# eZ-FET_lite.net
KiCad netlist of a schematic drawn in EAGLE
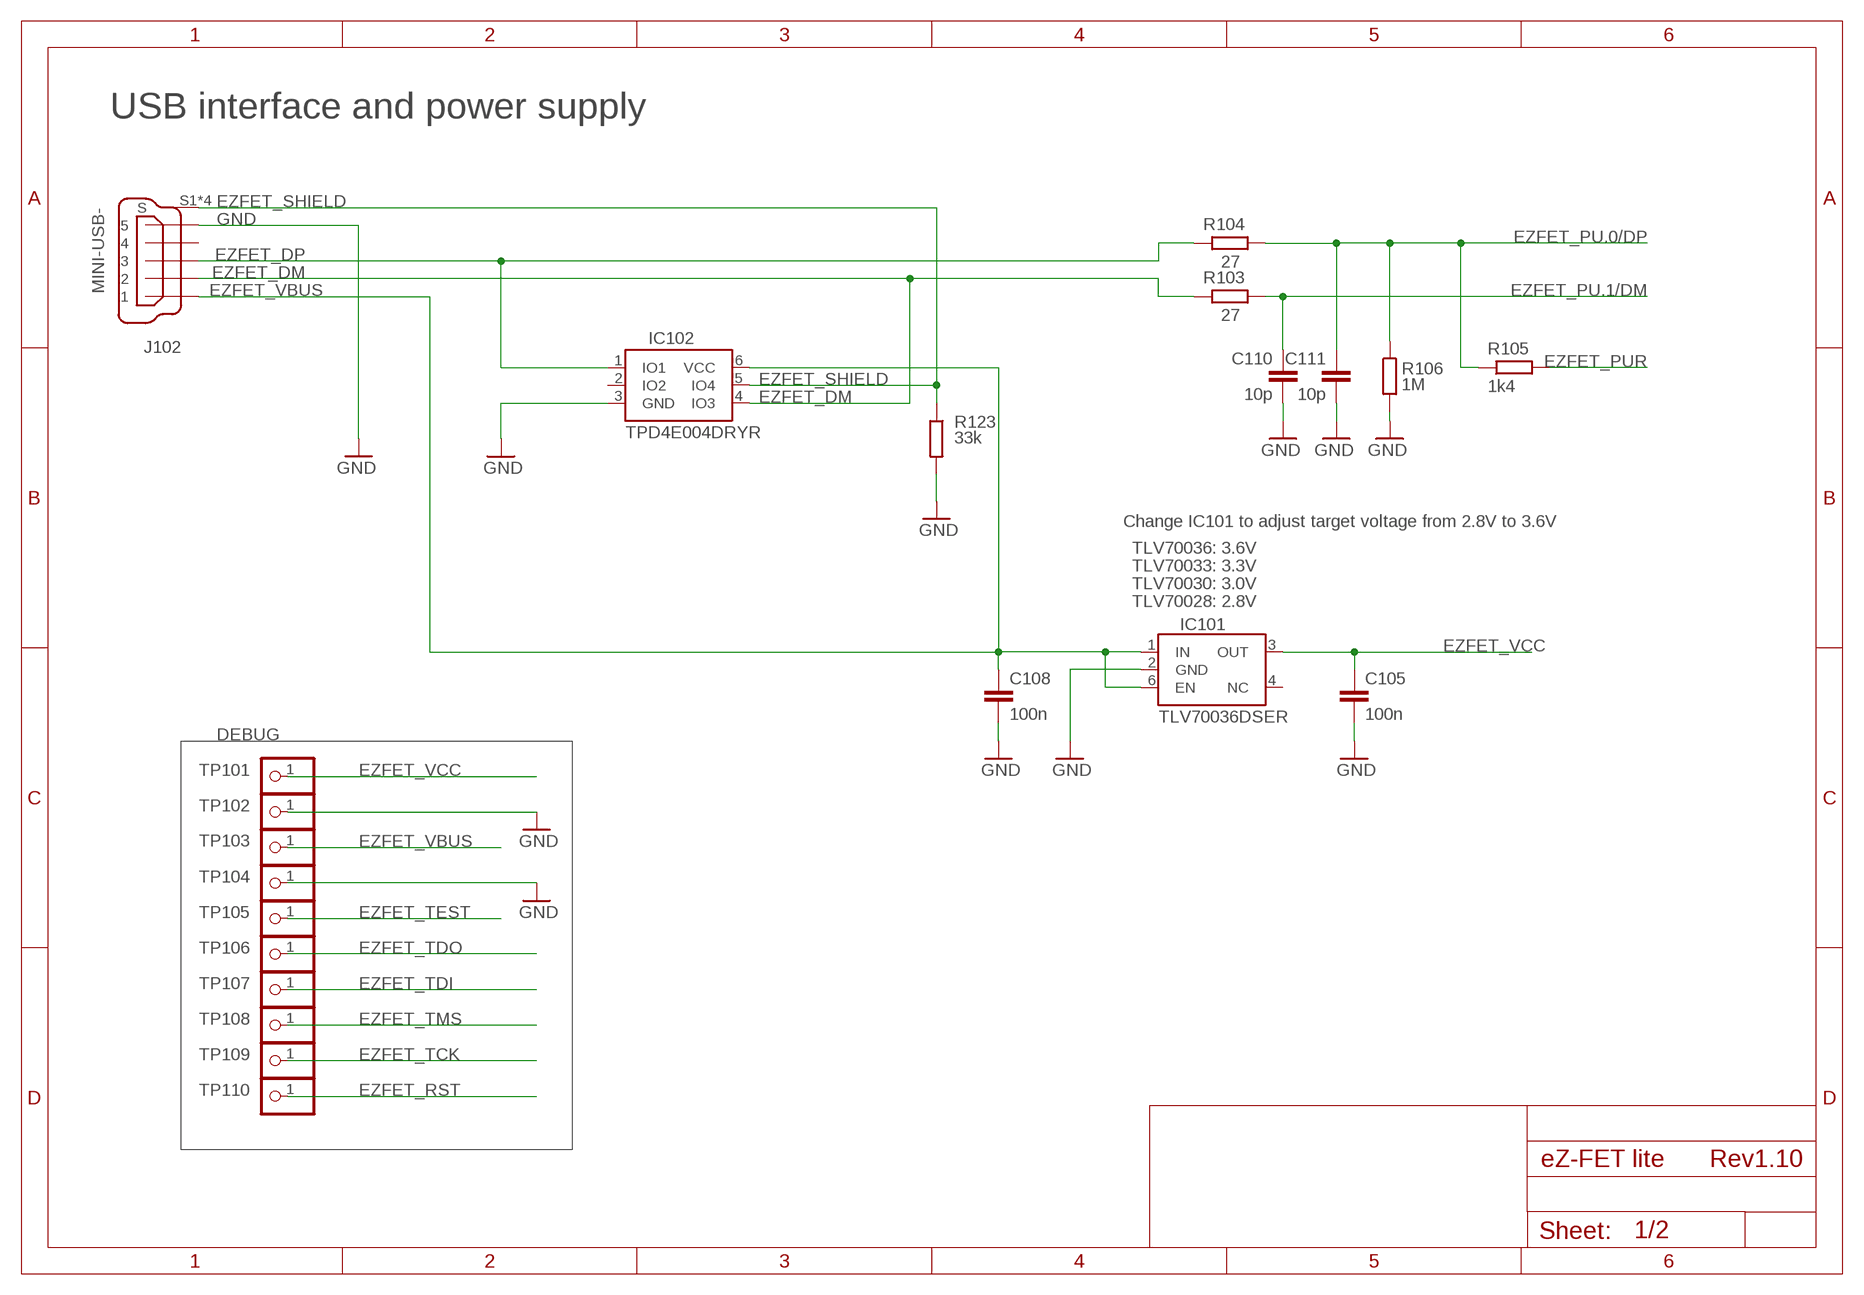
[diagram p0: schematic, sheet 1]
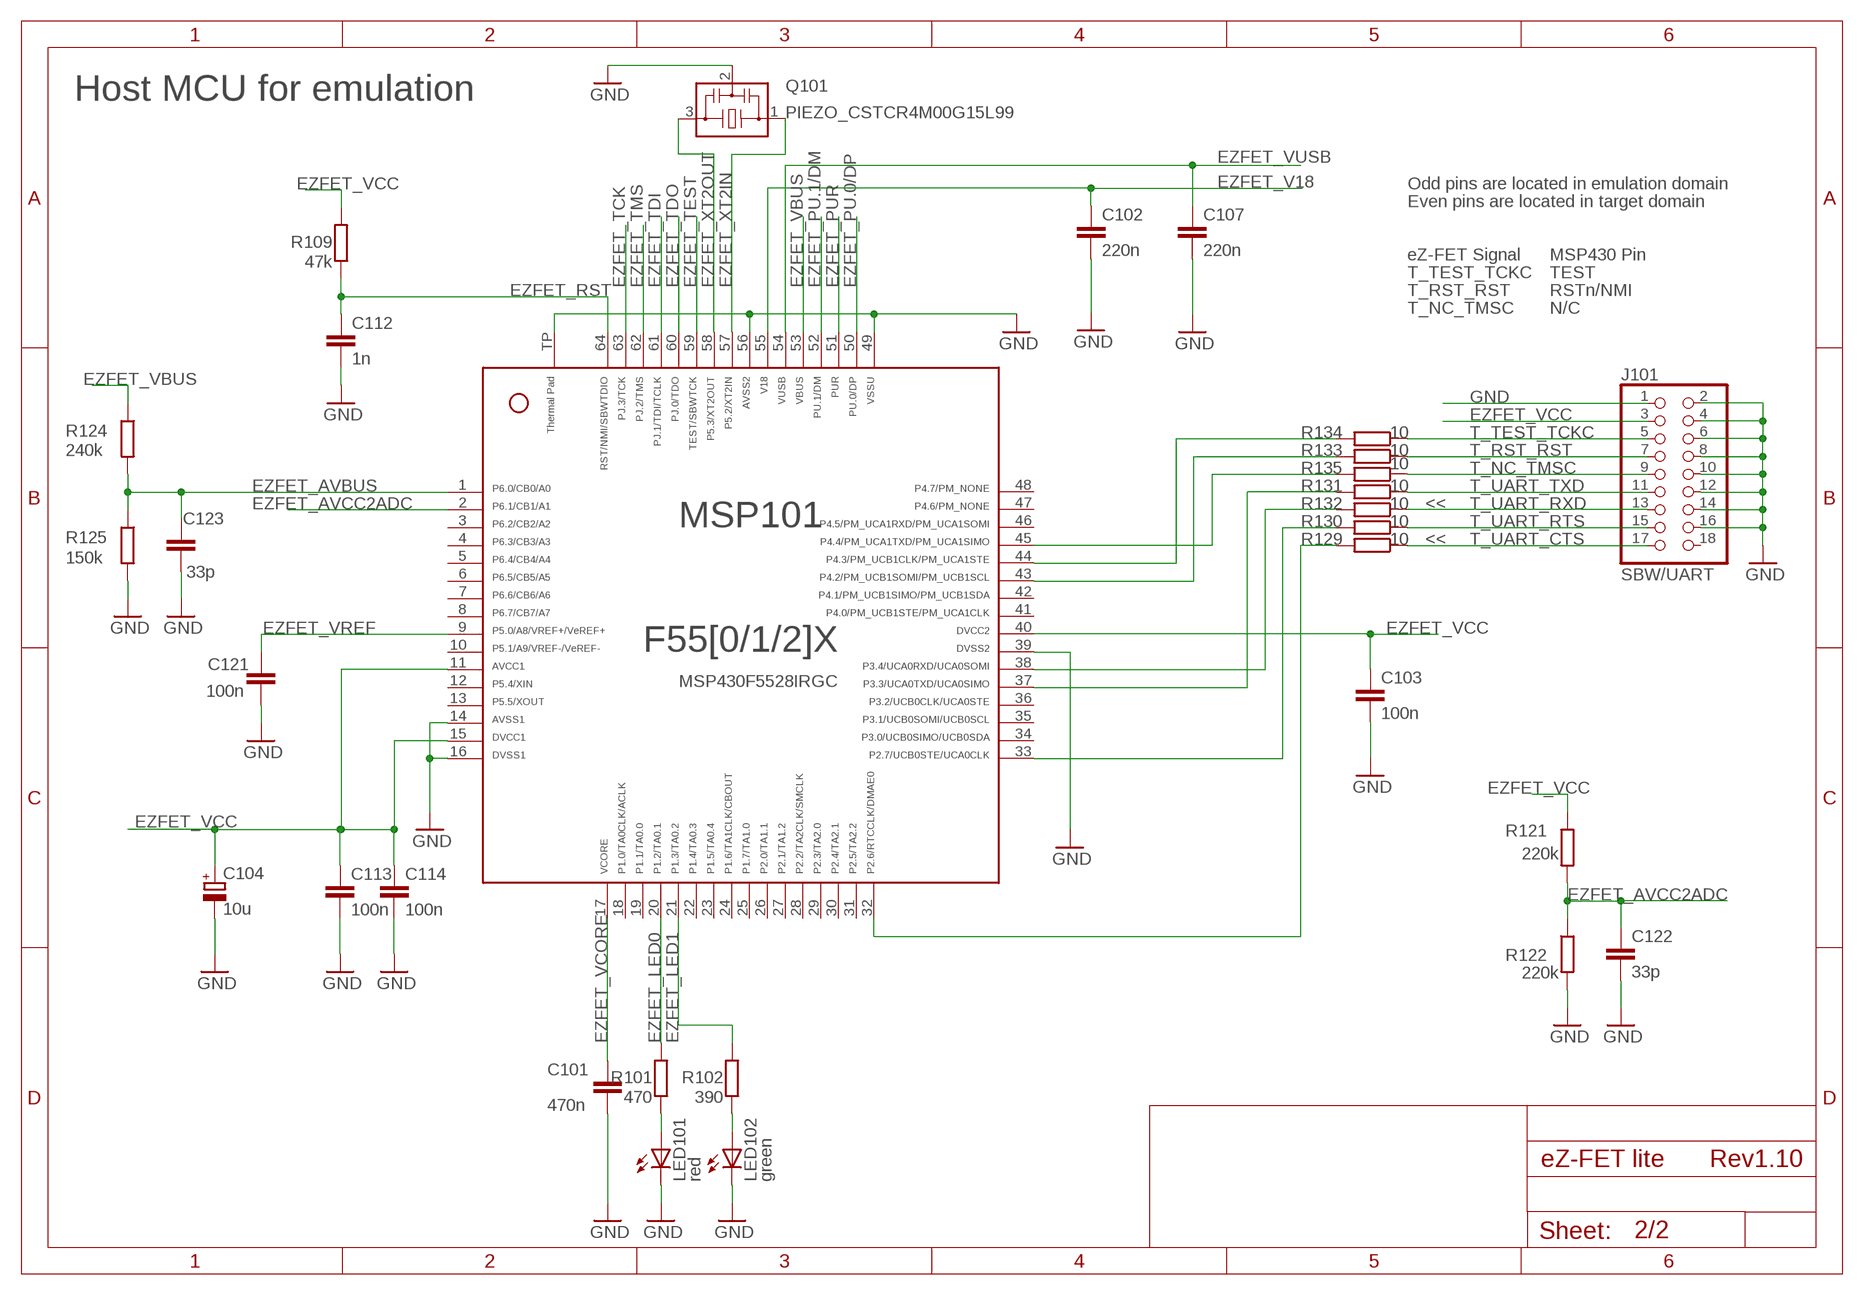
[diagram p1: schematic, sheet 2]

(export (version "E")
  (design (tool "Eeschema 10.0.6"))
  (components
    (comp (ref "C105")
      (value "100n")
      (footprint "eagle-import:C0402")
      (libsource (lib "eagle-import") (part "C-EUC0402"))
    )
    (comp (ref "C108")
      (value "100n")
      (footprint "eagle-import:C0402")
      (libsource (lib "eagle-import") (part "C-EUC0402"))
    )
    (comp (ref "C110")
      (value "10p")
      (footprint "eagle-import:C0402")
      (libsource (lib "eagle-import") (part "C-EUC0402"))
    )
    (comp (ref "C111")
      (value "10p")
      (footprint "eagle-import:C0402")
      (libsource (lib "eagle-import") (part "C-EUC0402"))
    )
    (comp (ref "IC101")
      (value "TLV70036DSER")
      (footprint "eagle-import:SON(DRY)6")
      (libsource (lib "eagle-import") (part "TLV700XX"))
    )
    (comp (ref "IC102")
      (value "TPD4E004DRYR")
      (footprint "eagle-import:SON(DRY)6")
      (libsource (lib "eagle-import") (part "TPD4E004"))
    )
    (comp (ref "J102")
      (value "MINI-USB-")
      (footprint "eagle-import:UX62M-B-5P")
      (libsource (lib "eagle-import") (part "MINI-USB-"))
    )
    (comp (ref "R103")
      (value "27")
      (footprint "eagle-import:R0402")
      (libsource (lib "eagle-import") (part "R-EU_R0402"))
    )
    (comp (ref "R104")
      (value "27")
      (footprint "eagle-import:R0402")
      (libsource (lib "eagle-import") (part "R-EU_R0402"))
    )
    (comp (ref "R105")
      (value "1k4")
      (footprint "eagle-import:R0402")
      (libsource (lib "eagle-import") (part "R-EU_R0402"))
    )
    (comp (ref "R106")
      (value "1M")
      (footprint "eagle-import:R0402")
      (libsource (lib "eagle-import") (part "R-EU_R0402"))
    )
    (comp (ref "R123")
      (value "33k")
      (footprint "eagle-import:R0402")
      (libsource (lib "eagle-import") (part "R-EU_R0402"))
    )
    (comp (ref "TP101")
      (value "TEST_PIN2")
      (footprint "eagle-import:1X01")
      (libsource (lib "eagle-import") (part "PINHD-1X1"))
    )
    (comp (ref "TP102")
      (value "TEST_PIN2")
      (footprint "eagle-import:1X01")
      (libsource (lib "eagle-import") (part "PINHD-1X1"))
    )
    (comp (ref "TP103")
      (value "TEST_PIN2")
      (footprint "eagle-import:1X01")
      (libsource (lib "eagle-import") (part "PINHD-1X1"))
    )
    (comp (ref "TP104")
      (value "TEST_PIN2")
      (footprint "eagle-import:1X01")
      (libsource (lib "eagle-import") (part "PINHD-1X1"))
    )
    (comp (ref "TP105")
      (value "TEST_PIN2")
      (footprint "eagle-import:1X01")
      (libsource (lib "eagle-import") (part "PINHD-1X1"))
    )
    (comp (ref "TP106")
      (value "TEST_PIN2")
      (footprint "eagle-import:1X01")
      (libsource (lib "eagle-import") (part "PINHD-1X1"))
    )
    (comp (ref "TP107")
      (value "TEST_PIN2")
      (footprint "eagle-import:1X01")
      (libsource (lib "eagle-import") (part "PINHD-1X1"))
    )
    (comp (ref "TP108")
      (value "TEST_PIN2")
      (footprint "eagle-import:1X01")
      (libsource (lib "eagle-import") (part "PINHD-1X1"))
    )
    (comp (ref "TP109")
      (value "TEST_PIN2")
      (footprint "eagle-import:1X01")
      (libsource (lib "eagle-import") (part "PINHD-1X1"))
    )
    (comp (ref "TP110")
      (value "TEST_PIN2")
      (footprint "eagle-import:1X01")
      (libsource (lib "eagle-import") (part "PINHD-1X1"))
    )
    (comp (ref "C101")
      (value "470n")
      (footprint "eagle-import:C0402")
      (libsource (lib "eagle-import") (part "C-EUC0402"))
    )
    (comp (ref "C102")
      (value "220n")
      (footprint "eagle-import:C0402")
      (libsource (lib "eagle-import") (part "C-EUC0402"))
    )
    (comp (ref "C103")
      (value "100n")
      (footprint "eagle-import:C0402")
      (libsource (lib "eagle-import") (part "C-EUC0402"))
    )
    (comp (ref "C104")
      (value "10u")
      (footprint "eagle-import:A_3216-18R")
      (libsource (lib "eagle-import") (part "CPOL-EUA/3216-18R"))
    )
    (comp (ref "C107")
      (value "220n")
      (footprint "eagle-import:C0402")
      (libsource (lib "eagle-import") (part "C-EUC0402"))
    )
    (comp (ref "C112")
      (value "1n")
      (footprint "eagle-import:C0402")
      (libsource (lib "eagle-import") (part "C-EUC0402"))
    )
    (comp (ref "C113")
      (value "100n")
      (footprint "eagle-import:C0402")
      (libsource (lib "eagle-import") (part "C-EUC0402"))
    )
    (comp (ref "C114")
      (value "100n")
      (footprint "eagle-import:C0402")
      (libsource (lib "eagle-import") (part "C-EUC0402"))
    )
    (comp (ref "C121")
      (value "100n")
      (footprint "eagle-import:C0402")
      (libsource (lib "eagle-import") (part "C-EUC0402"))
    )
    (comp (ref "C122")
      (value "33p")
      (footprint "eagle-import:C0402")
      (libsource (lib "eagle-import") (part "C-EUC0402"))
    )
    (comp (ref "C123")
      (value "33p")
      (footprint "eagle-import:C0402")
      (libsource (lib "eagle-import") (part "C-EUC0402"))
    )
    (comp (ref "J101")
      (value "SBW/UART")
      (footprint "eagle-import:2X09")
      (libsource (lib "eagle-import") (part "PINHD-2X9"))
    )
    (comp (ref "LED101")
      (value "red")
      (footprint "eagle-import:CHIP-LED0603")
      (libsource (lib "eagle-import") (part "LEDCHIP-LED0603"))
    )
    (comp (ref "LED102")
      (value "green")
      (footprint "eagle-import:CHIP-LED0603")
      (libsource (lib "eagle-import") (part "LEDCHIP-LED0603"))
    )
    (comp (ref "MSP101")
      (value "MSP430F5528IRGC")
      (footprint "eagle-import:RGC64")
      (libsource (lib "eagle-import") (part "F55[0/1/2]X---RGC64"))
    )
    (comp (ref "Q101")
      (value "PIEZO_CSTCR4M00G15L99")
      (footprint "eagle-import:CSTCR6M")
      (fields (field (name "MPN") "CSTCR6M00G53-R0"))
      (libsource (lib "eagle-import") (part "CSTCR6M00G53Z"))
    )
    (comp (ref "R101")
      (value "470")
      (footprint "eagle-import:R0402")
      (libsource (lib "eagle-import") (part "R-EU_R0402"))
    )
    (comp (ref "R102")
      (value "390")
      (footprint "eagle-import:R0402")
      (libsource (lib "eagle-import") (part "R-EU_R0402"))
    )
    (comp (ref "R109")
      (value "47k")
      (footprint "eagle-import:R0402")
      (libsource (lib "eagle-import") (part "R-EU_R0402"))
    )
    (comp (ref "R121")
      (value "220k")
      (footprint "eagle-import:R0402")
      (libsource (lib "eagle-import") (part "R-EU_R0402"))
    )
    (comp (ref "R122")
      (value "220k")
      (footprint "eagle-import:R0402")
      (libsource (lib "eagle-import") (part "R-EU_R0402"))
    )
    (comp (ref "R124")
      (value "240k")
      (footprint "eagle-import:R0402")
      (libsource (lib "eagle-import") (part "R-EU_R0402"))
    )
    (comp (ref "R125")
      (value "150k")
      (footprint "eagle-import:R0402")
      (libsource (lib "eagle-import") (part "R-EU_R0402"))
    )
    (comp (ref "R129")
      (value "10")
      (footprint "eagle-import:R0402")
      (libsource (lib "eagle-import") (part "R-EU_R0402"))
    )
    (comp (ref "R130")
      (value "10")
      (footprint "eagle-import:R0402")
      (libsource (lib "eagle-import") (part "R-EU_R0402"))
    )
    (comp (ref "R131")
      (value "10")
      (footprint "eagle-import:R0402")
      (libsource (lib "eagle-import") (part "R-EU_R0402"))
    )
    (comp (ref "R132")
      (value "10")
      (footprint "eagle-import:R0402")
      (libsource (lib "eagle-import") (part "R-EU_R0402"))
    )
    (comp (ref "R133")
      (value "10")
      (footprint "eagle-import:R0402")
      (libsource (lib "eagle-import") (part "R-EU_R0402"))
    )
    (comp (ref "R134")
      (value "10")
      (footprint "eagle-import:R0402")
      (libsource (lib "eagle-import") (part "R-EU_R0402"))
    )
    (comp (ref "R135")
      (value "10")
      (footprint "eagle-import:R0402")
      (libsource (lib "eagle-import") (part "R-EU_R0402"))
    )
  )
  (nets
    (net (code "1") (name "EZFET_AVBUS") (class "Default")
      (node (ref "C123") (pin "2") (pinfunction "2_2") (pintype "passive"))
      (node (ref "MSP101") (pin "1") (pinfunction "1_1") (pintype "bidirectional"))
      (node (ref "R124") (pin "2") (pinfunction "2_2") (pintype "passive"))
      (node (ref "R125") (pin "1") (pinfunction "1_1") (pintype "passive"))
    )
    (net (code "2") (name "EZFET_AVCC2ADC") (class "Default")
      (node (ref "C122") (pin "2") (pinfunction "2_2") (pintype "passive"))
      (node (ref "MSP101") (pin "2") (pinfunction "2_2") (pintype "bidirectional"))
      (node (ref "R121") (pin "2") (pinfunction "2_2") (pintype "passive"))
      (node (ref "R122") (pin "1") (pinfunction "1_1") (pintype "passive"))
    )
    (net (code "3") (name "EZFET_DM") (class "Default")
      (node (ref "IC102") (pin "4") (pinfunction "IO3_4") (pintype "bidirectional"))
      (node (ref "J102") (pin "2") (pinfunction "2_2") (pintype "input"))
      (node (ref "R103") (pin "1") (pinfunction "1_1") (pintype "passive"))
    )
    (net (code "4") (name "EZFET_DP") (class "Default")
      (node (ref "IC102") (pin "1") (pinfunction "IO1_1") (pintype "bidirectional"))
      (node (ref "J102") (pin "3") (pinfunction "3_3") (pintype "input"))
      (node (ref "R104") (pin "1") (pinfunction "1_1") (pintype "passive"))
    )
    (net (code "5") (name "EZFET_LED0") (class "Default")
      (node (ref "MSP101") (pin "20") (pinfunction "20_20") (pintype "bidirectional"))
      (node (ref "R101") (pin "2") (pinfunction "2_2") (pintype "passive"))
    )
    (net (code "6") (name "EZFET_LED1") (class "Default")
      (node (ref "MSP101") (pin "21") (pinfunction "21_21") (pintype "bidirectional"))
      (node (ref "R102") (pin "2") (pinfunction "2_2") (pintype "passive"))
    )
    (net (code "7") (name "EZFET_PU.0{slash}DP") (class "Default")
      (node (ref "C111") (pin "1") (pinfunction "1_1") (pintype "passive"))
      (node (ref "MSP101") (pin "50") (pinfunction "50_50") (pintype "bidirectional"))
      (node (ref "R104") (pin "2") (pinfunction "2_2") (pintype "passive"))
      (node (ref "R105") (pin "1") (pinfunction "1_1") (pintype "passive"))
      (node (ref "R106") (pin "1") (pinfunction "1_1") (pintype "passive"))
    )
    (net (code "8") (name "EZFET_PU.1{slash}DM") (class "Default")
      (node (ref "C110") (pin "1") (pinfunction "1_1") (pintype "passive"))
      (node (ref "MSP101") (pin "52") (pinfunction "52_52") (pintype "bidirectional"))
      (node (ref "R103") (pin "2") (pinfunction "2_2") (pintype "passive"))
    )
    (net (code "9") (name "EZFET_PUR") (class "Default")
      (node (ref "MSP101") (pin "51") (pinfunction "51_51") (pintype "bidirectional"))
      (node (ref "R105") (pin "2") (pinfunction "2_2") (pintype "passive"))
    )
    (net (code "10") (name "EZFET_RST") (class "Default")
      (node (ref "C112") (pin "1") (pinfunction "1_1") (pintype "passive"))
      (node (ref "MSP101") (pin "64") (pinfunction "64_64") (pintype "bidirectional"))
      (node (ref "R109") (pin "1") (pinfunction "1_1") (pintype "passive"))
      (node (ref "TP110") (pin "1") (pinfunction "1_1") (pintype "passive"))
    )
    (net (code "11") (name "EZFET_SHIELD") (class "Default")
      (node (ref "IC102") (pin "5") (pinfunction "IO4_5") (pintype "bidirectional"))
      (node (ref "J102") (pin "S1") (pinfunction "S_S1") (pintype "input"))
      (node (ref "J102") (pin "S2") (pinfunction "S_S2") (pintype "input"))
      (node (ref "J102") (pin "S3") (pinfunction "S_S3") (pintype "input"))
      (node (ref "J102") (pin "S4") (pinfunction "S_S4") (pintype "input"))
      (node (ref "R123") (pin "1") (pinfunction "1_1") (pintype "passive"))
    )
    (net (code "12") (name "EZFET_TCK") (class "Default")
      (node (ref "MSP101") (pin "63") (pinfunction "63_63") (pintype "bidirectional"))
      (node (ref "TP109") (pin "1") (pinfunction "1_1") (pintype "passive"))
    )
    (net (code "13") (name "EZFET_TDI") (class "Default")
      (node (ref "MSP101") (pin "61") (pinfunction "61_61") (pintype "bidirectional"))
      (node (ref "TP107") (pin "1") (pinfunction "1_1") (pintype "passive"))
    )
    (net (code "14") (name "EZFET_TDO") (class "Default")
      (node (ref "MSP101") (pin "60") (pinfunction "60_60") (pintype "bidirectional"))
      (node (ref "TP106") (pin "1") (pinfunction "1_1") (pintype "passive"))
    )
    (net (code "15") (name "EZFET_TEST") (class "Default")
      (node (ref "MSP101") (pin "59") (pinfunction "59_59") (pintype "input"))
      (node (ref "TP105") (pin "1") (pinfunction "1_1") (pintype "passive"))
    )
    (net (code "16") (name "EZFET_TMS") (class "Default")
      (node (ref "MSP101") (pin "62") (pinfunction "62_62") (pintype "bidirectional"))
      (node (ref "TP108") (pin "1") (pinfunction "1_1") (pintype "passive"))
    )
    (net (code "17") (name "EZFET_V18") (class "Default")
      (node (ref "C102") (pin "1") (pinfunction "1_1") (pintype "passive"))
      (node (ref "MSP101") (pin "55") (pinfunction "55_55") (pintype "power_in"))
    )
    (net (code "18") (name "EZFET_VBUS") (class "Default")
      (node (ref "C108") (pin "1") (pinfunction "1_1") (pintype "passive"))
      (node (ref "IC101") (pin "1") (pinfunction "IN_1") (pintype "power_in"))
      (node (ref "IC101") (pin "6") (pinfunction "EN_6") (pintype "input"))
      (node (ref "IC102") (pin "6") (pinfunction "VCC_6") (pintype "power_in"))
      (node (ref "J102") (pin "1") (pinfunction "1_1") (pintype "input"))
      (node (ref "MSP101") (pin "53") (pinfunction "53_53") (pintype "power_in"))
      (node (ref "R124") (pin "1") (pinfunction "1_1") (pintype "passive"))
      (node (ref "TP103") (pin "1") (pinfunction "1_1") (pintype "passive"))
    )
    (net (code "19") (name "EZFET_VCC") (class "Default")
      (node (ref "C103") (pin "1") (pinfunction "1_1") (pintype "passive"))
      (node (ref "C104") (pin "+") (pinfunction "+_+") (pintype "passive"))
      (node (ref "C105") (pin "1") (pinfunction "1_1") (pintype "passive"))
      (node (ref "C113") (pin "1") (pinfunction "1_1") (pintype "passive"))
      (node (ref "C114") (pin "1") (pinfunction "1_1") (pintype "passive"))
      (node (ref "IC101") (pin "3") (pinfunction "OUT_3") (pintype "power_in"))
      (node (ref "J101") (pin "3") (pinfunction "3_3") (pintype "passive"))
      (node (ref "MSP101") (pin "11") (pinfunction "11_11") (pintype "power_in"))
      (node (ref "MSP101") (pin "15") (pinfunction "15_15") (pintype "power_in"))
      (node (ref "MSP101") (pin "40") (pinfunction "40_40") (pintype "power_in"))
      (node (ref "R109") (pin "2") (pinfunction "2_2") (pintype "passive"))
      (node (ref "R121") (pin "1") (pinfunction "1_1") (pintype "passive"))
      (node (ref "TP101") (pin "1") (pinfunction "1_1") (pintype "passive"))
    )
    (net (code "20") (name "EZFET_VCORE") (class "Default")
      (node (ref "C101") (pin "1") (pinfunction "1_1") (pintype "passive"))
      (node (ref "MSP101") (pin "17") (pinfunction "17_17") (pintype "power_in"))
    )
    (net (code "21") (name "EZFET_VREF") (class "Default")
      (node (ref "C121") (pin "1") (pinfunction "1_1") (pintype "passive"))
      (node (ref "MSP101") (pin "9") (pinfunction "9_9") (pintype "bidirectional"))
    )
    (net (code "22") (name "EZFET_VUSB") (class "Default")
      (node (ref "C107") (pin "1") (pinfunction "1_1") (pintype "passive"))
      (node (ref "MSP101") (pin "54") (pinfunction "54_54") (pintype "power_in"))
    )
    (net (code "23") (name "EZFET_XT2IN") (class "Default")
      (node (ref "MSP101") (pin "57") (pinfunction "57_57") (pintype "bidirectional"))
      (node (ref "Q101") (pin "1") (pinfunction "1_1") (pintype "passive"))
    )
    (net (code "24") (name "EZFET_XT2OUT") (class "Default")
      (node (ref "MSP101") (pin "58") (pinfunction "58_58") (pintype "bidirectional"))
      (node (ref "Q101") (pin "3") (pinfunction "3_3") (pintype "passive"))
    )
    (net (code "25") (name "GND") (class "Default")
      (node (ref "C101") (pin "2") (pinfunction "2_2") (pintype "passive"))
      (node (ref "C102") (pin "2") (pinfunction "2_2") (pintype "passive"))
      (node (ref "C103") (pin "2") (pinfunction "2_2") (pintype "passive"))
      (node (ref "C104") (pin "-") (pinfunction "-_-") (pintype "passive"))
      (node (ref "C105") (pin "2") (pinfunction "2_2") (pintype "passive"))
      (node (ref "C107") (pin "2") (pinfunction "2_2") (pintype "passive"))
      (node (ref "C108") (pin "2") (pinfunction "2_2") (pintype "passive"))
      (node (ref "C110") (pin "2") (pinfunction "2_2") (pintype "passive"))
      (node (ref "C111") (pin "2") (pinfunction "2_2") (pintype "passive"))
      (node (ref "C112") (pin "2") (pinfunction "2_2") (pintype "passive"))
      (node (ref "C113") (pin "2") (pinfunction "2_2") (pintype "passive"))
      (node (ref "C114") (pin "2") (pinfunction "2_2") (pintype "passive"))
      (node (ref "C121") (pin "2") (pinfunction "2_2") (pintype "passive"))
      (node (ref "C122") (pin "1") (pinfunction "1_1") (pintype "passive"))
      (node (ref "C123") (pin "1") (pinfunction "1_1") (pintype "passive"))
      (node (ref "IC101") (pin "2") (pinfunction "GND_2") (pintype "power_in"))
      (node (ref "IC102") (pin "3") (pinfunction "GND_3") (pintype "power_in"))
      (node (ref "J101") (pin "1") (pinfunction "1_1") (pintype "passive"))
      (node (ref "J101") (pin "10") (pinfunction "10_10") (pintype "passive"))
      (node (ref "J101") (pin "12") (pinfunction "12_12") (pintype "passive"))
      (node (ref "J101") (pin "14") (pinfunction "14_14") (pintype "passive"))
      (node (ref "J101") (pin "16") (pinfunction "16_16") (pintype "passive"))
      (node (ref "J101") (pin "2") (pinfunction "2_2") (pintype "passive"))
      (node (ref "J101") (pin "4") (pinfunction "4_4") (pintype "passive"))
      (node (ref "J101") (pin "6") (pinfunction "6_6") (pintype "passive"))
      (node (ref "J101") (pin "8") (pinfunction "8_8") (pintype "passive"))
      (node (ref "J102") (pin "5") (pinfunction "5_5") (pintype "input"))
      (node (ref "LED101") (pin "C") (pinfunction "C_C") (pintype "passive"))
      (node (ref "LED102") (pin "C") (pinfunction "C_C") (pintype "passive"))
      (node (ref "MSP101") (pin "14") (pinfunction "14_14") (pintype "power_in"))
      (node (ref "MSP101") (pin "16") (pinfunction "16_16") (pintype "power_in"))
      (node (ref "MSP101") (pin "39") (pinfunction "39_39") (pintype "power_in"))
      (node (ref "MSP101") (pin "49") (pinfunction "49_49") (pintype "power_in"))
      (node (ref "MSP101") (pin "56") (pinfunction "56_56") (pintype "power_in"))
      (node (ref "MSP101") (pin "TP") (pinfunction "TP_TP") (pintype "power_in"))
      (node (ref "Q101") (pin "2") (pinfunction "2_2") (pintype "passive"))
      (node (ref "R106") (pin "2") (pinfunction "2_2") (pintype "passive"))
      (node (ref "R122") (pin "2") (pinfunction "2_2") (pintype "passive"))
      (node (ref "R123") (pin "2") (pinfunction "2_2") (pintype "passive"))
      (node (ref "R125") (pin "2") (pinfunction "2_2") (pintype "passive"))
      (node (ref "TP102") (pin "1") (pinfunction "1_1") (pintype "passive"))
      (node (ref "TP104") (pin "1") (pinfunction "1_1") (pintype "passive"))
    )
    (net (code "26") (name "Net-(LED101-PadA)") (class "Default")
      (node (ref "LED101") (pin "A") (pinfunction "A_A") (pintype "passive"))
      (node (ref "R101") (pin "1") (pinfunction "1_1") (pintype "passive"))
    )
    (net (code "27") (name "Net-(LED102-PadA)") (class "Default")
      (node (ref "LED102") (pin "A") (pinfunction "A_A") (pintype "passive"))
      (node (ref "R102") (pin "1") (pinfunction "1_1") (pintype "passive"))
    )
    (net (code "28") (name "Net-(MSP101-Pad32)") (class "Default")
      (node (ref "MSP101") (pin "32") (pinfunction "32_32") (pintype "bidirectional"))
      (node (ref "R129") (pin "2") (pinfunction "2_2") (pintype "passive"))
    )
    (net (code "29") (name "Net-(MSP101-Pad33)") (class "Default")
      (node (ref "MSP101") (pin "33") (pinfunction "33_33") (pintype "bidirectional"))
      (node (ref "R130") (pin "2") (pinfunction "2_2") (pintype "passive"))
    )
    (net (code "30") (name "Net-(MSP101-Pad37)") (class "Default")
      (node (ref "MSP101") (pin "37") (pinfunction "37_37") (pintype "bidirectional"))
      (node (ref "R131") (pin "2") (pinfunction "2_2") (pintype "passive"))
    )
    (net (code "31") (name "Net-(MSP101-Pad38)") (class "Default")
      (node (ref "MSP101") (pin "38") (pinfunction "38_38") (pintype "bidirectional"))
      (node (ref "R132") (pin "2") (pinfunction "2_2") (pintype "passive"))
    )
    (net (code "32") (name "Net-(MSP101-Pad43)") (class "Default")
      (node (ref "MSP101") (pin "43") (pinfunction "43_43") (pintype "bidirectional"))
      (node (ref "R133") (pin "2") (pinfunction "2_2") (pintype "passive"))
    )
    (net (code "33") (name "Net-(MSP101-Pad44)") (class "Default")
      (node (ref "MSP101") (pin "44") (pinfunction "44_44") (pintype "bidirectional"))
      (node (ref "R134") (pin "2") (pinfunction "2_2") (pintype "passive"))
    )
    (net (code "34") (name "Net-(MSP101-Pad45)") (class "Default")
      (node (ref "MSP101") (pin "45") (pinfunction "45_45") (pintype "bidirectional"))
      (node (ref "R135") (pin "2") (pinfunction "2_2") (pintype "passive"))
    )
    (net (code "35") (name "T_NC_TMSC") (class "Default")
      (node (ref "J101") (pin "9") (pinfunction "9_9") (pintype "passive"))
      (node (ref "R135") (pin "1") (pinfunction "1_1") (pintype "passive"))
    )
    (net (code "36") (name "T_RST_RST") (class "Default")
      (node (ref "J101") (pin "7") (pinfunction "7_7") (pintype "passive"))
      (node (ref "R133") (pin "1") (pinfunction "1_1") (pintype "passive"))
    )
    (net (code "37") (name "T_TEST_TCKC") (class "Default")
      (node (ref "J101") (pin "5") (pinfunction "5_5") (pintype "passive"))
      (node (ref "R134") (pin "1") (pinfunction "1_1") (pintype "passive"))
    )
    (net (code "38") (name "T_UART_CTS") (class "Default")
      (node (ref "J101") (pin "17") (pinfunction "17_17") (pintype "passive"))
      (node (ref "R129") (pin "1") (pinfunction "1_1") (pintype "passive"))
    )
    (net (code "39") (name "T_UART_RTS") (class "Default")
      (node (ref "J101") (pin "15") (pinfunction "15_15") (pintype "passive"))
      (node (ref "R130") (pin "1") (pinfunction "1_1") (pintype "passive"))
    )
    (net (code "40") (name "T_UART_RXD") (class "Default")
      (node (ref "J101") (pin "13") (pinfunction "13_13") (pintype "passive"))
      (node (ref "R132") (pin "1") (pinfunction "1_1") (pintype "passive"))
    )
    (net (code "41") (name "T_UART_TXD") (class "Default")
      (node (ref "J101") (pin "11") (pinfunction "11_11") (pintype "passive"))
      (node (ref "R131") (pin "1") (pinfunction "1_1") (pintype "passive"))
    )
    (net (code "42") (name "unconnected-(IC101-NC-Pad4)") (class "Default")
      (node (ref "IC101") (pin "4") (pinfunction "NC_4") (pintype "no_connect"))
    )
    (net (code "43") (name "unconnected-(IC102-IO2-Pad2)") (class "Default")
      (node (ref "IC102") (pin "2") (pinfunction "IO2_2") (pintype "bidirectional"))
    )
    (net (code "44") (name "unconnected-(J101-Pad18)") (class "Default")
      (node (ref "J101") (pin "18") (pinfunction "18_18") (pintype "passive"))
    )
    (net (code "45") (name "unconnected-(J102-Pad4)") (class "Default")
      (node (ref "J102") (pin "4") (pinfunction "4_4") (pintype "input"))
    )
    (net (code "46") (name "unconnected-(MSP101-Pad3)") (class "Default")
      (node (ref "MSP101") (pin "3") (pinfunction "3_3") (pintype "bidirectional"))
    )
    (net (code "47") (name "unconnected-(MSP101-Pad4)") (class "Default")
      (node (ref "MSP101") (pin "4") (pinfunction "4_4") (pintype "bidirectional"))
    )
    (net (code "48") (name "unconnected-(MSP101-Pad5)") (class "Default")
      (node (ref "MSP101") (pin "5") (pinfunction "5_5") (pintype "bidirectional"))
    )
    (net (code "49") (name "unconnected-(MSP101-Pad6)") (class "Default")
      (node (ref "MSP101") (pin "6") (pinfunction "6_6") (pintype "bidirectional"))
    )
    (net (code "50") (name "unconnected-(MSP101-Pad7)") (class "Default")
      (node (ref "MSP101") (pin "7") (pinfunction "7_7") (pintype "bidirectional"))
    )
    (net (code "51") (name "unconnected-(MSP101-Pad8)") (class "Default")
      (node (ref "MSP101") (pin "8") (pinfunction "8_8") (pintype "bidirectional"))
    )
    (net (code "52") (name "unconnected-(MSP101-Pad10)") (class "Default")
      (node (ref "MSP101") (pin "10") (pinfunction "10_10") (pintype "bidirectional"))
    )
    (net (code "53") (name "unconnected-(MSP101-Pad12)") (class "Default")
      (node (ref "MSP101") (pin "12") (pinfunction "12_12") (pintype "bidirectional"))
    )
    (net (code "54") (name "unconnected-(MSP101-Pad13)") (class "Default")
      (node (ref "MSP101") (pin "13") (pinfunction "13_13") (pintype "bidirectional"))
    )
    (net (code "55") (name "unconnected-(MSP101-Pad18)") (class "Default")
      (node (ref "MSP101") (pin "18") (pinfunction "18_18") (pintype "bidirectional"))
    )
    (net (code "56") (name "unconnected-(MSP101-Pad19)") (class "Default")
      (node (ref "MSP101") (pin "19") (pinfunction "19_19") (pintype "bidirectional"))
    )
    (net (code "57") (name "unconnected-(MSP101-Pad22)") (class "Default")
      (node (ref "MSP101") (pin "22") (pinfunction "22_22") (pintype "bidirectional"))
    )
    (net (code "58") (name "unconnected-(MSP101-Pad23)") (class "Default")
      (node (ref "MSP101") (pin "23") (pinfunction "23_23") (pintype "bidirectional"))
    )
    (net (code "59") (name "unconnected-(MSP101-Pad24)") (class "Default")
      (node (ref "MSP101") (pin "24") (pinfunction "24_24") (pintype "bidirectional"))
    )
    (net (code "60") (name "unconnected-(MSP101-Pad25)") (class "Default")
      (node (ref "MSP101") (pin "25") (pinfunction "25_25") (pintype "bidirectional"))
    )
    (net (code "61") (name "unconnected-(MSP101-Pad26)") (class "Default")
      (node (ref "MSP101") (pin "26") (pinfunction "26_26") (pintype "bidirectional"))
    )
    (net (code "62") (name "unconnected-(MSP101-Pad27)") (class "Default")
      (node (ref "MSP101") (pin "27") (pinfunction "27_27") (pintype "bidirectional"))
    )
    (net (code "63") (name "unconnected-(MSP101-Pad28)") (class "Default")
      (node (ref "MSP101") (pin "28") (pinfunction "28_28") (pintype "bidirectional"))
    )
    (net (code "64") (name "unconnected-(MSP101-Pad29)") (class "Default")
      (node (ref "MSP101") (pin "29") (pinfunction "29_29") (pintype "bidirectional"))
    )
    (net (code "65") (name "unconnected-(MSP101-Pad30)") (class "Default")
      (node (ref "MSP101") (pin "30") (pinfunction "30_30") (pintype "bidirectional"))
    )
    (net (code "66") (name "unconnected-(MSP101-Pad31)") (class "Default")
      (node (ref "MSP101") (pin "31") (pinfunction "31_31") (pintype "bidirectional"))
    )
    (net (code "67") (name "unconnected-(MSP101-Pad34)") (class "Default")
      (node (ref "MSP101") (pin "34") (pinfunction "34_34") (pintype "bidirectional"))
    )
    (net (code "68") (name "unconnected-(MSP101-Pad35)") (class "Default")
      (node (ref "MSP101") (pin "35") (pinfunction "35_35") (pintype "bidirectional"))
    )
    (net (code "69") (name "unconnected-(MSP101-Pad36)") (class "Default")
      (node (ref "MSP101") (pin "36") (pinfunction "36_36") (pintype "bidirectional"))
    )
    (net (code "70") (name "unconnected-(MSP101-Pad41)") (class "Default")
      (node (ref "MSP101") (pin "41") (pinfunction "41_41") (pintype "bidirectional"))
    )
    (net (code "71") (name "unconnected-(MSP101-Pad42)") (class "Default")
      (node (ref "MSP101") (pin "42") (pinfunction "42_42") (pintype "bidirectional"))
    )
    (net (code "72") (name "unconnected-(MSP101-Pad46)") (class "Default")
      (node (ref "MSP101") (pin "46") (pinfunction "46_46") (pintype "bidirectional"))
    )
    (net (code "73") (name "unconnected-(MSP101-Pad47)") (class "Default")
      (node (ref "MSP101") (pin "47") (pinfunction "47_47") (pintype "bidirectional"))
    )
    (net (code "74") (name "unconnected-(MSP101-Pad48)") (class "Default")
      (node (ref "MSP101") (pin "48") (pinfunction "48_48") (pintype "bidirectional"))
    )
  )
)
